# Arduino_Due.net
KiCad netlist of a schematic drawn in Altium Designer
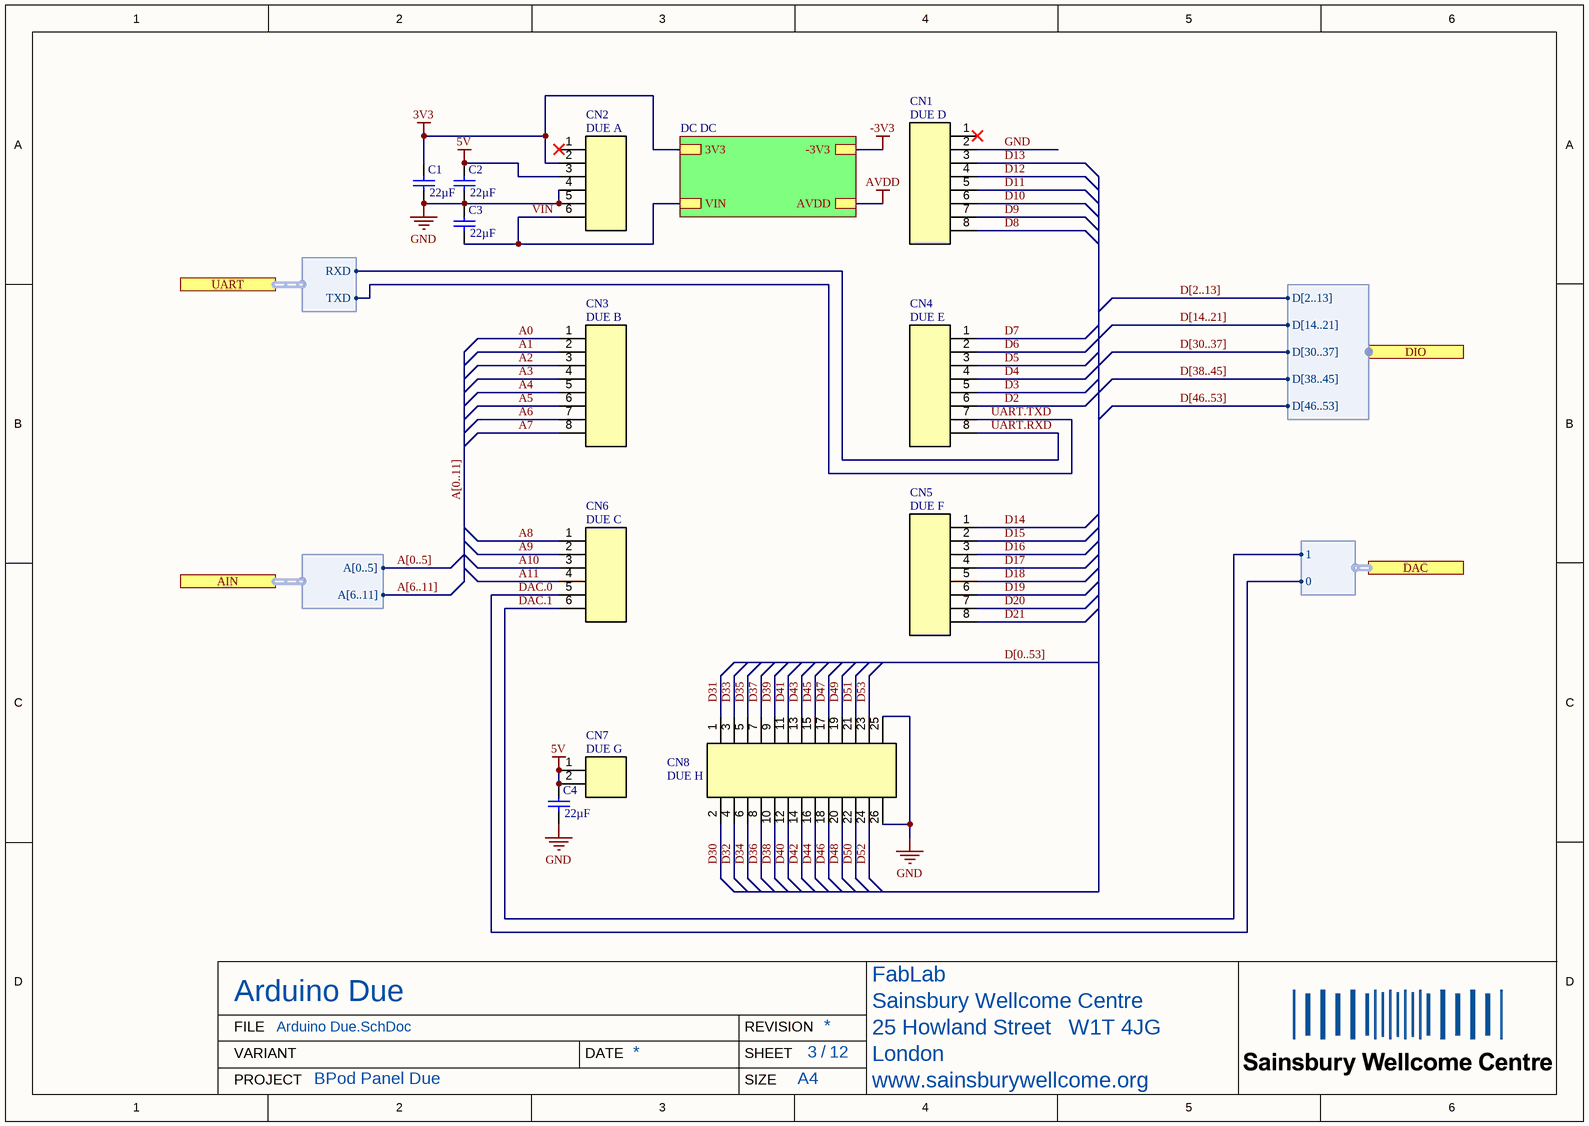
[diagram p0: Arduino Due.SchDoc]

(export (version "E")
  (design (tool "Eeschema 10.0.6"))
  (components
    (comp (ref "C1")
      (value "22µF")
      (footprint "CAP_CHIP_0805")
      (description "0805 Multilayer Ceramic Capacitors MLCC")
      (fields (field (name "TOLERANCE") "20%") (field (name "PARTNUMBER") "CL21A226MAQNNNE"))
      (libsource (lib "Sainsbury Wellcome Centre") (part "Cap"))
    )
    (comp (ref "C2")
      (value "22µF")
      (footprint "CAP_CHIP_0805")
      (description "0805 Multilayer Ceramic Capacitors MLCC")
      (fields (field (name "TOLERANCE") "20%") (field (name "PARTNUMBER") "CL21A226MAQNNNE"))
      (libsource (lib "Sainsbury Wellcome Centre") (part "Cap"))
    )
    (comp (ref "C3")
      (value "22µF")
      (footprint "CAP_CHIP_0805")
      (description "0805 Multilayer Ceramic Capacitors MLCC")
      (fields (field (name "TOLERANCE") "20%") (field (name "PARTNUMBER") "CL21A226MAQNNNE"))
      (libsource (lib "Sainsbury Wellcome Centre") (part "Cap"))
    )
    (comp (ref "C4")
      (value "22µF")
      (footprint "CAP_CHIP_0805")
      (description "0805 Multilayer Ceramic Capacitors MLCC")
      (fields (field (name "TOLERANCE") "20%") (field (name "PARTNUMBER") "CL21A226MAQNNNE"))
      (libsource (lib "Sainsbury Wellcome Centre") (part "Cap"))
    )
    (comp (ref "CN1")
      (value "DUE D")
      (footprint "PIN_2.54_1X8P")
      (fields (field (name "PARTNUMBER") "PZ254V-11-08P"))
      (libsource (lib "Sainsbury Wellcome Centre") (part "Header_1X8P"))
    )
    (comp (ref "CN2")
      (value "DUE A")
      (footprint "PIN_2.54_1X6P")
      (fields (field (name "PARTNUMBER") "PZ254V-11-06P"))
      (libsource (lib "Sainsbury Wellcome Centre") (part "Header_1X6P"))
    )
    (comp (ref "CN3")
      (value "DUE B")
      (footprint "PIN_2.54_1X8P")
      (fields (field (name "PARTNUMBER") "PZ254V-11-08P"))
      (libsource (lib "") (part "Header_1X8P_1"))
    )
    (comp (ref "CN4")
      (value "DUE E")
      (footprint "PIN_2.54_1X8P")
      (fields (field (name "PARTNUMBER") "PZ254V-11-08P"))
      (libsource (lib "Sainsbury Wellcome Centre") (part "Header_1X8P"))
    )
    (comp (ref "CN5")
      (value "DUE F")
      (footprint "PIN_2.54_1X8P")
      (fields (field (name "PARTNUMBER") "PZ254V-11-08P"))
      (libsource (lib "Sainsbury Wellcome Centre") (part "Header_1X8P"))
    )
    (comp (ref "CN6")
      (value "DUE C")
      (footprint "PIN_2.54_1X6P")
      (fields (field (name "PARTNUMBER") "PZ254V-11-06P"))
      (libsource (lib "Sainsbury Wellcome Centre") (part "Header_1X6P"))
    )
    (comp (ref "CN7")
      (value "DUE G")
      (footprint "PIN_2.54_1X2P")
      (fields (field (name "PARTNUMBER") "PZ254V-11-02P"))
      (libsource (lib "Sainsbury Wellcome Centre") (part "Header_1X2P"))
    )
    (comp (ref "CN8")
      (value "DUE H")
      (footprint "PIN_2.54_2X13P")
      (fields (field (name "PARTNUMBER") "PZ254-2-13-Z-8.5"))
      (libsource (lib "Sainsbury Wellcome Centre") (part "Header_2X13P"))
    )
  )
  (nets
    (net (code "16") (name "/A0") (class "Default")
      (node (ref "CN3") (pin "1") (pinfunction "1_1") (pintype "passive"))
    )
    (net (code "17") (name "/A1") (class "Default")
      (node (ref "CN3") (pin "2") (pinfunction "2_2") (pintype "passive"))
    )
    (net (code "18") (name "/A2") (class "Default")
      (node (ref "CN3") (pin "3") (pinfunction "3_3") (pintype "passive"))
    )
    (net (code "19") (name "/A3") (class "Default")
      (node (ref "CN3") (pin "4") (pinfunction "4_4") (pintype "passive"))
    )
    (net (code "20") (name "/A4") (class "Default")
      (node (ref "CN3") (pin "5") (pinfunction "5_5") (pintype "passive"))
    )
    (net (code "21") (name "/A5") (class "Default")
      (node (ref "CN3") (pin "6") (pinfunction "6_6") (pintype "passive"))
    )
    (net (code "22") (name "/A6") (class "Default")
      (node (ref "CN3") (pin "7") (pinfunction "7_7") (pintype "passive"))
    )
    (net (code "23") (name "/A7") (class "Default")
      (node (ref "CN3") (pin "8") (pinfunction "8_8") (pintype "passive"))
    )
    (net (code "24") (name "/A8") (class "Default")
      (node (ref "CN6") (pin "1") (pinfunction "1_1") (pintype "passive"))
    )
    (net (code "25") (name "/A9") (class "Default")
      (node (ref "CN6") (pin "2") (pinfunction "2_2") (pintype "passive"))
    )
    (net (code "26") (name "/A10") (class "Default")
      (node (ref "CN6") (pin "3") (pinfunction "3_3") (pintype "passive"))
    )
    (net (code "27") (name "/A11") (class "Default")
      (node (ref "CN6") (pin "4") (pinfunction "4_4") (pintype "passive"))
    )
    (net (code "31") (name "/D2") (class "Default")
      (node (ref "CN4") (pin "6") (pinfunction "6_6") (pintype "passive"))
    )
    (net (code "32") (name "/D3") (class "Default")
      (node (ref "CN4") (pin "5") (pinfunction "5_5") (pintype "passive"))
    )
    (net (code "33") (name "/D4") (class "Default")
      (node (ref "CN4") (pin "4") (pinfunction "4_4") (pintype "passive"))
    )
    (net (code "34") (name "/D5") (class "Default")
      (node (ref "CN4") (pin "3") (pinfunction "3_3") (pintype "passive"))
    )
    (net (code "35") (name "/D6") (class "Default")
      (node (ref "CN4") (pin "2") (pinfunction "2_2") (pintype "passive"))
    )
    (net (code "36") (name "/D7") (class "Default")
      (node (ref "CN4") (pin "1") (pinfunction "1_1") (pintype "passive"))
    )
    (net (code "37") (name "/D8") (class "Default")
      (node (ref "CN1") (pin "8") (pinfunction "8_8") (pintype "passive"))
    )
    (net (code "38") (name "/D9") (class "Default")
      (node (ref "CN1") (pin "7") (pinfunction "7_7") (pintype "passive"))
    )
    (net (code "39") (name "/D10") (class "Default")
      (node (ref "CN1") (pin "6") (pinfunction "6_6") (pintype "passive"))
    )
    (net (code "40") (name "/D11") (class "Default")
      (node (ref "CN1") (pin "5") (pinfunction "5_5") (pintype "passive"))
    )
    (net (code "41") (name "/D12") (class "Default")
      (node (ref "CN1") (pin "4") (pinfunction "4_4") (pintype "passive"))
    )
    (net (code "42") (name "/D13") (class "Default")
      (node (ref "CN1") (pin "3") (pinfunction "3_3") (pintype "passive"))
    )
    (net (code "43") (name "/D14") (class "Default")
      (node (ref "CN5") (pin "1") (pinfunction "1_1") (pintype "passive"))
    )
    (net (code "44") (name "/D15") (class "Default")
      (node (ref "CN5") (pin "2") (pinfunction "2_2") (pintype "passive"))
    )
    (net (code "45") (name "/D16") (class "Default")
      (node (ref "CN5") (pin "3") (pinfunction "3_3") (pintype "passive"))
    )
    (net (code "46") (name "/D17") (class "Default")
      (node (ref "CN5") (pin "4") (pinfunction "4_4") (pintype "passive"))
    )
    (net (code "47") (name "/D18") (class "Default")
      (node (ref "CN5") (pin "5") (pinfunction "5_5") (pintype "passive"))
    )
    (net (code "48") (name "/D19") (class "Default")
      (node (ref "CN5") (pin "6") (pinfunction "6_6") (pintype "passive"))
    )
    (net (code "49") (name "/D20") (class "Default")
      (node (ref "CN5") (pin "7") (pinfunction "7_7") (pintype "passive"))
    )
    (net (code "50") (name "/D21") (class "Default")
      (node (ref "CN5") (pin "8") (pinfunction "8_8") (pintype "passive"))
    )
    (net (code "51") (name "/D30") (class "Default")
      (node (ref "CN8") (pin "2") (pinfunction "2_2") (pintype "passive"))
    )
    (net (code "52") (name "/D31") (class "Default")
      (node (ref "CN8") (pin "1") (pinfunction "1_1") (pintype "passive"))
    )
    (net (code "53") (name "/D32") (class "Default")
      (node (ref "CN8") (pin "4") (pinfunction "4_4") (pintype "passive"))
    )
    (net (code "54") (name "/D33") (class "Default")
      (node (ref "CN8") (pin "3") (pinfunction "3_3") (pintype "passive"))
    )
    (net (code "55") (name "/D34") (class "Default")
      (node (ref "CN8") (pin "6") (pinfunction "6_6") (pintype "passive"))
    )
    (net (code "56") (name "/D35") (class "Default")
      (node (ref "CN8") (pin "5") (pinfunction "5_5") (pintype "passive"))
    )
    (net (code "57") (name "/D36") (class "Default")
      (node (ref "CN8") (pin "8") (pinfunction "8_8") (pintype "passive"))
    )
    (net (code "58") (name "/D37") (class "Default")
      (node (ref "CN8") (pin "7") (pinfunction "7_7") (pintype "passive"))
    )
    (net (code "59") (name "/D38") (class "Default")
      (node (ref "CN8") (pin "10") (pinfunction "10_10") (pintype "passive"))
    )
    (net (code "60") (name "/D39") (class "Default")
      (node (ref "CN8") (pin "9") (pinfunction "9_9") (pintype "passive"))
    )
    (net (code "61") (name "/D40") (class "Default")
      (node (ref "CN8") (pin "12") (pinfunction "12_12") (pintype "passive"))
    )
    (net (code "62") (name "/D41") (class "Default")
      (node (ref "CN8") (pin "11") (pinfunction "11_11") (pintype "passive"))
    )
    (net (code "63") (name "/D42") (class "Default")
      (node (ref "CN8") (pin "14") (pinfunction "14_14") (pintype "passive"))
    )
    (net (code "64") (name "/D43") (class "Default")
      (node (ref "CN8") (pin "13") (pinfunction "13_13") (pintype "passive"))
    )
    (net (code "65") (name "/D44") (class "Default")
      (node (ref "CN8") (pin "16") (pinfunction "16_16") (pintype "passive"))
    )
    (net (code "66") (name "/D45") (class "Default")
      (node (ref "CN8") (pin "15") (pinfunction "15_15") (pintype "passive"))
    )
    (net (code "67") (name "/D46") (class "Default")
      (node (ref "CN8") (pin "18") (pinfunction "18_18") (pintype "passive"))
    )
    (net (code "68") (name "/D47") (class "Default")
      (node (ref "CN8") (pin "17") (pinfunction "17_17") (pintype "passive"))
    )
    (net (code "69") (name "/D48") (class "Default")
      (node (ref "CN8") (pin "20") (pinfunction "20_20") (pintype "passive"))
    )
    (net (code "70") (name "/D49") (class "Default")
      (node (ref "CN8") (pin "19") (pinfunction "19_19") (pintype "passive"))
    )
    (net (code "71") (name "/D50") (class "Default")
      (node (ref "CN8") (pin "22") (pinfunction "22_22") (pintype "passive"))
    )
    (net (code "72") (name "/D51") (class "Default")
      (node (ref "CN8") (pin "21") (pinfunction "21_21") (pintype "passive"))
    )
    (net (code "73") (name "/D52") (class "Default")
      (node (ref "CN8") (pin "24") (pinfunction "24_24") (pintype "passive"))
    )
    (net (code "74") (name "/D53") (class "Default")
      (node (ref "CN8") (pin "23") (pinfunction "23_23") (pintype "passive"))
    )
    (net (code "75") (name "/DAC.0") (class "Default")
      (node (ref "CN6") (pin "5") (pinfunction "5_5") (pintype "passive"))
    )
    (net (code "76") (name "/DAC.1") (class "Default")
      (node (ref "CN6") (pin "6") (pinfunction "6_6") (pintype "passive"))
    )
    (net (code "83") (name "/UART.RXD") (class "Default")
      (node (ref "CN4") (pin "8") (pinfunction "8_8") (pintype "passive"))
    )
    (net (code "84") (name "/UART.TXD") (class "Default")
      (node (ref "CN4") (pin "7") (pinfunction "7_7") (pintype "passive"))
    )
    (net (code "85") (name "/VIN") (class "Default")
      (node (ref "C3") (pin "1") (pinfunction "1_1") (pintype "passive"))
      (node (ref "CN2") (pin "6") (pinfunction "6_6") (pintype "passive"))
    )
    (net (code "90") (name "3V3") (class "Default")
      (node (ref "C1") (pin "2") (pinfunction "2_2") (pintype "passive"))
      (node (ref "CN2") (pin "2") (pinfunction "2_2") (pintype "passive"))
    )
    (net (code "91") (name "5V") (class "Default")
      (node (ref "C2") (pin "2") (pinfunction "2_2") (pintype "passive"))
      (node (ref "C4") (pin "2") (pinfunction "2_2") (pintype "passive"))
      (node (ref "CN2") (pin "3") (pinfunction "3_3") (pintype "passive"))
      (node (ref "CN7") (pin "1") (pinfunction "1_1") (pintype "passive"))
      (node (ref "CN7") (pin "2") (pinfunction "2_2") (pintype "passive"))
    )
    (net (code "93") (name "GND") (class "Default")
      (node (ref "C1") (pin "1") (pinfunction "1_1") (pintype "passive"))
      (node (ref "C2") (pin "1") (pinfunction "1_1") (pintype "passive"))
      (node (ref "C3") (pin "2") (pinfunction "2_2") (pintype "passive"))
      (node (ref "C4") (pin "1") (pinfunction "1_1") (pintype "passive"))
      (node (ref "CN1") (pin "2") (pinfunction "2_2") (pintype "passive"))
      (node (ref "CN2") (pin "4") (pinfunction "4_4") (pintype "passive"))
      (node (ref "CN2") (pin "5") (pinfunction "5_5") (pintype "passive"))
      (node (ref "CN8") (pin "25") (pinfunction "25_25") (pintype "passive"))
      (node (ref "CN8") (pin "26") (pinfunction "26_26") (pintype "passive"))
    )
    (net (code "94") (name "unconnected-(CN1-Pad1)") (class "Default")
      (node (ref "CN1") (pin "1") (pinfunction "1_1") (pintype "passive+no_connect"))
    )
    (net (code "95") (name "unconnected-(CN2-Pad1)") (class "Default")
      (node (ref "CN2") (pin "1") (pinfunction "1_1") (pintype "passive+no_connect"))
    )
  )
)
